# Schematic.net
KiCad netlist of a schematic drawn in Altium Designer
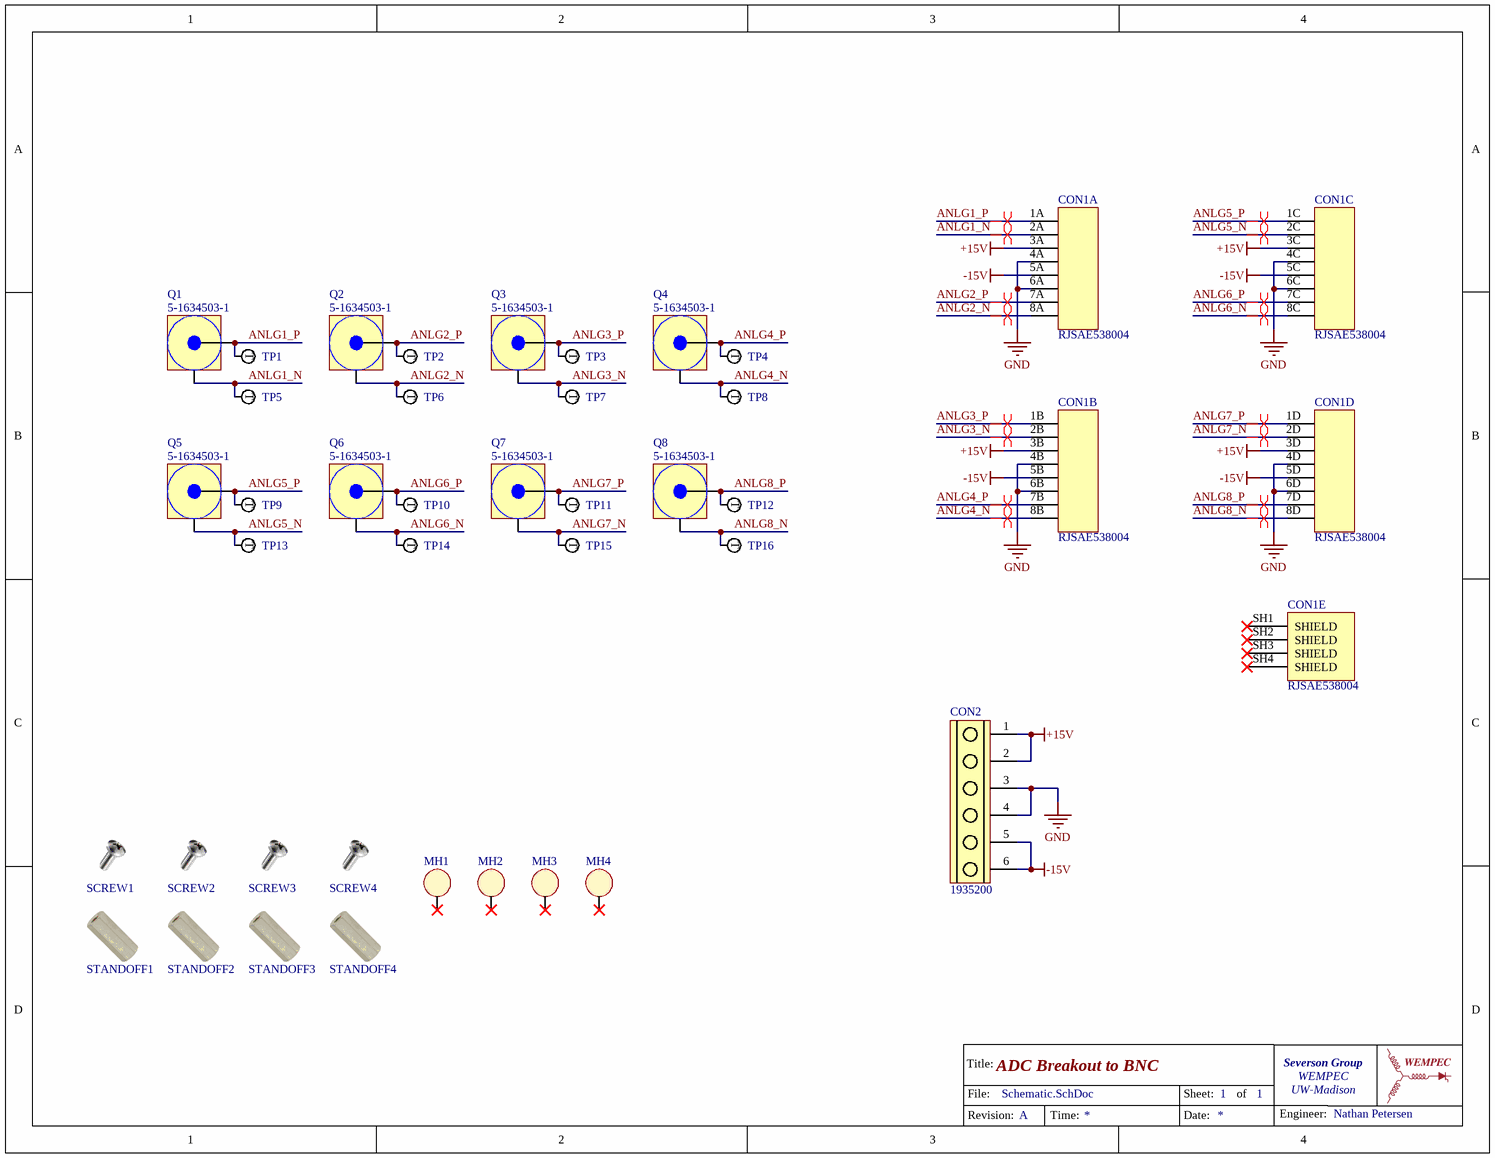
[diagram p0: Schematic.SchDoc]

(export (version "E")
  (design (tool "Eeschema 10.0.6"))
  (components
    (comp (ref "*1") (value "TitleBlockWEMPEC") (libsource (lib "AMDC") (part "TitleBlockWEMPEC")))
    (comp (ref "CON1")
      (value "RJSAE538004")
      (footprint "RJSAE538004")
      (description "CONN MOD JACK 8P8C R/A SHIELDED")
      (libsource (lib "AMDC") (part "RJSAE538004"))
    )
    (comp (ref "CON2")
      (value "1935200")
      (footprint "1935200")
      (description "TERM BLK 6POS SIDE ENTRY 5MM PCB")
      (libsource (lib "Schlib1") (part "1935200"))
    )
    (comp (ref "MH1")
      (value "MOUNT_HOLE")
      (footprint "AMDC:MOUNTING_HOLE")
      (description "MOUNTING HOLE")
      (libsource (lib "AMDC") (part "MOUNT_HOLE"))
    )
    (comp (ref "MH2")
      (value "MOUNT_HOLE")
      (footprint "AMDC:MOUNTING_HOLE")
      (description "MOUNTING HOLE")
      (libsource (lib "AMDC") (part "MOUNT_HOLE"))
    )
    (comp (ref "MH3")
      (value "MOUNT_HOLE")
      (footprint "AMDC:MOUNTING_HOLE")
      (description "MOUNTING HOLE")
      (libsource (lib "AMDC") (part "MOUNT_HOLE"))
    )
    (comp (ref "MH4")
      (value "MOUNT_HOLE")
      (footprint "AMDC:MOUNTING_HOLE")
      (description "MOUNTING HOLE")
      (libsource (lib "AMDC") (part "MOUNT_HOLE"))
    )
    (comp (ref "Q1")
      (value "5-1634503-1")
      (footprint "PcbLib:5-1634503-1")
      (description "BNC Connector Jack, Female Socket 50 Ohm Through Hole Solder")
      (libsource (lib "Schlib1") (part "5-1634503-1"))
    )
    (comp (ref "Q2")
      (value "5-1634503-1")
      (footprint "PcbLib:5-1634503-1")
      (description "BNC Connector Jack, Female Socket 50 Ohm Through Hole Solder")
      (libsource (lib "Schlib1") (part "5-1634503-1"))
    )
    (comp (ref "Q3")
      (value "5-1634503-1")
      (footprint "PcbLib:5-1634503-1")
      (description "BNC Connector Jack, Female Socket 50 Ohm Through Hole Solder")
      (libsource (lib "Schlib1") (part "5-1634503-1"))
    )
    (comp (ref "Q4")
      (value "5-1634503-1")
      (footprint "PcbLib:5-1634503-1")
      (description "BNC Connector Jack, Female Socket 50 Ohm Through Hole Solder")
      (libsource (lib "Schlib1") (part "5-1634503-1"))
    )
    (comp (ref "Q5")
      (value "5-1634503-1")
      (footprint "PcbLib:5-1634503-1")
      (description "BNC Connector Jack, Female Socket 50 Ohm Through Hole Solder")
      (libsource (lib "Schlib1") (part "5-1634503-1"))
    )
    (comp (ref "Q6")
      (value "5-1634503-1")
      (footprint "PcbLib:5-1634503-1")
      (description "BNC Connector Jack, Female Socket 50 Ohm Through Hole Solder")
      (libsource (lib "Schlib1") (part "5-1634503-1"))
    )
    (comp (ref "Q7")
      (value "5-1634503-1")
      (footprint "PcbLib:5-1634503-1")
      (description "BNC Connector Jack, Female Socket 50 Ohm Through Hole Solder")
      (libsource (lib "Schlib1") (part "5-1634503-1"))
    )
    (comp (ref "Q8")
      (value "5-1634503-1")
      (footprint "PcbLib:5-1634503-1")
      (description "BNC Connector Jack, Female Socket 50 Ohm Through Hole Solder")
      (libsource (lib "Schlib1") (part "5-1634503-1"))
    )
    (comp (ref "SCREW1") (value "Screw-4-40") (libsource (lib "AMDC") (part "Screw-4-40")))
    (comp (ref "SCREW2") (value "Screw-4-40") (libsource (lib "AMDC") (part "Screw-4-40")))
    (comp (ref "SCREW3") (value "Screw-4-40") (libsource (lib "AMDC") (part "Screw-4-40")))
    (comp (ref "SCREW4") (value "Screw-4-40") (libsource (lib "AMDC") (part "Screw-4-40")))
    (comp (ref "STANDOFF1") (value "Standoff-4-40") (libsource (lib "AMDC") (part "Standoff-4-40")))
    (comp (ref "STANDOFF2") (value "Standoff-4-40") (libsource (lib "AMDC") (part "Standoff-4-40")))
    (comp (ref "STANDOFF3") (value "Standoff-4-40") (libsource (lib "AMDC") (part "Standoff-4-40")))
    (comp (ref "STANDOFF4") (value "Standoff-4-40") (libsource (lib "AMDC") (part "Standoff-4-40")))
    (comp (ref "TP1")
      (value "Test Point")
      (footprint "TP_1.6MM")
      (libsource (lib "AMDC") (part "Test Point"))
    )
    (comp (ref "TP2")
      (value "Test Point")
      (footprint "TP_1.6MM")
      (libsource (lib "AMDC") (part "Test Point"))
    )
    (comp (ref "TP3")
      (value "Test Point")
      (footprint "TP_1.6MM")
      (libsource (lib "AMDC") (part "Test Point"))
    )
    (comp (ref "TP4")
      (value "Test Point")
      (footprint "TP_1.6MM")
      (libsource (lib "AMDC") (part "Test Point"))
    )
    (comp (ref "TP5")
      (value "Test Point")
      (footprint "TP_1.6MM")
      (libsource (lib "AMDC") (part "Test Point"))
    )
    (comp (ref "TP6")
      (value "Test Point")
      (footprint "TP_1.6MM")
      (libsource (lib "AMDC") (part "Test Point"))
    )
    (comp (ref "TP7")
      (value "Test Point")
      (footprint "TP_1.6MM")
      (libsource (lib "AMDC") (part "Test Point"))
    )
    (comp (ref "TP8")
      (value "Test Point")
      (footprint "TP_1.6MM")
      (libsource (lib "AMDC") (part "Test Point"))
    )
    (comp (ref "TP9")
      (value "Test Point")
      (footprint "TP_1.6MM")
      (libsource (lib "AMDC") (part "Test Point"))
    )
    (comp (ref "TP10")
      (value "Test Point")
      (footprint "TP_1.6MM")
      (libsource (lib "AMDC") (part "Test Point"))
    )
    (comp (ref "TP11")
      (value "Test Point")
      (footprint "TP_1.6MM")
      (libsource (lib "AMDC") (part "Test Point"))
    )
    (comp (ref "TP12")
      (value "Test Point")
      (footprint "TP_1.6MM")
      (libsource (lib "AMDC") (part "Test Point"))
    )
    (comp (ref "TP13")
      (value "Test Point")
      (footprint "TP_1.6MM")
      (libsource (lib "AMDC") (part "Test Point"))
    )
    (comp (ref "TP14")
      (value "Test Point")
      (footprint "TP_1.6MM")
      (libsource (lib "AMDC") (part "Test Point"))
    )
    (comp (ref "TP15")
      (value "Test Point")
      (footprint "TP_1.6MM")
      (libsource (lib "AMDC") (part "Test Point"))
    )
    (comp (ref "TP16")
      (value "Test Point")
      (footprint "TP_1.6MM")
      (libsource (lib "AMDC") (part "Test Point"))
    )
  )
  (nets
    (net (code "1") (name "+15V") (class "Default")
      (node (ref "CON1") (pin "3A") (pinfunction "79_3A") (pintype "passive"))
      (node (ref "CON1") (pin "3B") (pinfunction "79_3B") (pintype "passive"))
      (node (ref "CON1") (pin "3C") (pinfunction "79_3C") (pintype "passive"))
      (node (ref "CON1") (pin "3D") (pinfunction "79_3D") (pintype "passive"))
      (node (ref "CON2") (pin "1") (pinfunction "1_1") (pintype "passive"))
      (node (ref "CON2") (pin "2") (pinfunction "2_2") (pintype "passive"))
    )
    (net (code "2") (name "-15V") (class "Default")
      (node (ref "CON1") (pin "5A") (pinfunction "79_5A") (pintype "passive"))
      (node (ref "CON1") (pin "5B") (pinfunction "79_5B") (pintype "passive"))
      (node (ref "CON1") (pin "5C") (pinfunction "79_5C") (pintype "passive"))
      (node (ref "CON1") (pin "5D") (pinfunction "79_5D") (pintype "passive"))
      (node (ref "CON2") (pin "5") (pinfunction "5_5") (pintype "passive"))
      (node (ref "CON2") (pin "6") (pinfunction "6_6") (pintype "passive"))
    )
    (net (code "3") (name "/ANLG1_N") (class "Default")
      (node (ref "CON1") (pin "2A") (pinfunction "79_2A") (pintype "passive"))
      (node (ref "Q1") (pin "2") (pinfunction "2_2") (pintype "passive"))
      (node (ref "TP5") (pin "1") (pinfunction "1_1") (pintype "passive"))
    )
    (net (code "4") (name "/ANLG1_P") (class "Default")
      (node (ref "CON1") (pin "1A") (pinfunction "79_1A") (pintype "passive"))
      (node (ref "Q1") (pin "1") (pinfunction "1_1") (pintype "passive"))
      (node (ref "TP1") (pin "1") (pinfunction "1_1") (pintype "passive"))
    )
    (net (code "5") (name "/ANLG2_N") (class "Default")
      (node (ref "CON1") (pin "8A") (pinfunction "79_8A") (pintype "passive"))
      (node (ref "Q2") (pin "2") (pinfunction "2_2") (pintype "passive"))
      (node (ref "TP6") (pin "1") (pinfunction "1_1") (pintype "passive"))
    )
    (net (code "6") (name "/ANLG2_P") (class "Default")
      (node (ref "CON1") (pin "7A") (pinfunction "79_7A") (pintype "passive"))
      (node (ref "Q2") (pin "1") (pinfunction "1_1") (pintype "passive"))
      (node (ref "TP2") (pin "1") (pinfunction "1_1") (pintype "passive"))
    )
    (net (code "7") (name "/ANLG3_N") (class "Default")
      (node (ref "CON1") (pin "2B") (pinfunction "79_2B") (pintype "passive"))
      (node (ref "Q3") (pin "2") (pinfunction "2_2") (pintype "passive"))
      (node (ref "TP7") (pin "1") (pinfunction "1_1") (pintype "passive"))
    )
    (net (code "8") (name "/ANLG3_P") (class "Default")
      (node (ref "CON1") (pin "1B") (pinfunction "79_1B") (pintype "passive"))
      (node (ref "Q3") (pin "1") (pinfunction "1_1") (pintype "passive"))
      (node (ref "TP3") (pin "1") (pinfunction "1_1") (pintype "passive"))
    )
    (net (code "9") (name "/ANLG4_N") (class "Default")
      (node (ref "CON1") (pin "8B") (pinfunction "79_8B") (pintype "passive"))
      (node (ref "Q4") (pin "2") (pinfunction "2_2") (pintype "passive"))
      (node (ref "TP8") (pin "1") (pinfunction "1_1") (pintype "passive"))
    )
    (net (code "10") (name "/ANLG4_P") (class "Default")
      (node (ref "CON1") (pin "7B") (pinfunction "79_7B") (pintype "passive"))
      (node (ref "Q4") (pin "1") (pinfunction "1_1") (pintype "passive"))
      (node (ref "TP4") (pin "1") (pinfunction "1_1") (pintype "passive"))
    )
    (net (code "11") (name "/ANLG5_N") (class "Default")
      (node (ref "CON1") (pin "2C") (pinfunction "79_2C") (pintype "passive"))
      (node (ref "Q5") (pin "2") (pinfunction "2_2") (pintype "passive"))
      (node (ref "TP13") (pin "1") (pinfunction "1_1") (pintype "passive"))
    )
    (net (code "12") (name "/ANLG5_P") (class "Default")
      (node (ref "CON1") (pin "1C") (pinfunction "79_1C") (pintype "passive"))
      (node (ref "Q5") (pin "1") (pinfunction "1_1") (pintype "passive"))
      (node (ref "TP9") (pin "1") (pinfunction "1_1") (pintype "passive"))
    )
    (net (code "13") (name "/ANLG6_N") (class "Default")
      (node (ref "CON1") (pin "8C") (pinfunction "79_8C") (pintype "passive"))
      (node (ref "Q6") (pin "2") (pinfunction "2_2") (pintype "passive"))
      (node (ref "TP14") (pin "1") (pinfunction "1_1") (pintype "passive"))
    )
    (net (code "14") (name "/ANLG6_P") (class "Default")
      (node (ref "CON1") (pin "7C") (pinfunction "79_7C") (pintype "passive"))
      (node (ref "Q6") (pin "1") (pinfunction "1_1") (pintype "passive"))
      (node (ref "TP10") (pin "1") (pinfunction "1_1") (pintype "passive"))
    )
    (net (code "15") (name "/ANLG7_N") (class "Default")
      (node (ref "CON1") (pin "2D") (pinfunction "79_2D") (pintype "passive"))
      (node (ref "Q7") (pin "2") (pinfunction "2_2") (pintype "passive"))
      (node (ref "TP15") (pin "1") (pinfunction "1_1") (pintype "passive"))
    )
    (net (code "16") (name "/ANLG7_P") (class "Default")
      (node (ref "CON1") (pin "1D") (pinfunction "79_1D") (pintype "passive"))
      (node (ref "Q7") (pin "1") (pinfunction "1_1") (pintype "passive"))
      (node (ref "TP11") (pin "1") (pinfunction "1_1") (pintype "passive"))
    )
    (net (code "17") (name "/ANLG8_N") (class "Default")
      (node (ref "CON1") (pin "8D") (pinfunction "79_8D") (pintype "passive"))
      (node (ref "Q8") (pin "2") (pinfunction "2_2") (pintype "passive"))
      (node (ref "TP16") (pin "1") (pinfunction "1_1") (pintype "passive"))
    )
    (net (code "18") (name "/ANLG8_P") (class "Default")
      (node (ref "CON1") (pin "7D") (pinfunction "79_7D") (pintype "passive"))
      (node (ref "Q8") (pin "1") (pinfunction "1_1") (pintype "passive"))
      (node (ref "TP12") (pin "1") (pinfunction "1_1") (pintype "passive"))
    )
    (net (code "19") (name "GND") (class "Default")
      (node (ref "CON1") (pin "4A") (pinfunction "79_4A") (pintype "passive"))
      (node (ref "CON1") (pin "4B") (pinfunction "79_4B") (pintype "passive"))
      (node (ref "CON1") (pin "4C") (pinfunction "79_4C") (pintype "passive"))
      (node (ref "CON1") (pin "4D") (pinfunction "79_4D") (pintype "passive"))
      (node (ref "CON1") (pin "6A") (pinfunction "79_6A") (pintype "passive"))
      (node (ref "CON1") (pin "6B") (pinfunction "79_6B") (pintype "passive"))
      (node (ref "CON1") (pin "6C") (pinfunction "79_6C") (pintype "passive"))
      (node (ref "CON1") (pin "6D") (pinfunction "79_6D") (pintype "passive"))
      (node (ref "CON2") (pin "3") (pinfunction "3_3") (pintype "passive"))
      (node (ref "CON2") (pin "4") (pinfunction "4_4") (pintype "passive"))
    )
    (net (code "20") (name "unconnected-(CON1E-SHIELD-PadSH1)") (class "Default")
      (node (ref "CON1") (pin "SH1") (pinfunction "SHIELD_SH1") (pintype "passive+no_connect"))
    )
    (net (code "21") (name "unconnected-(CON1E-SHIELD-PadSH2)") (class "Default")
      (node (ref "CON1") (pin "SH2") (pinfunction "SHIELD_SH2") (pintype "passive+no_connect"))
    )
    (net (code "22") (name "unconnected-(CON1E-SHIELD-PadSH3)") (class "Default")
      (node (ref "CON1") (pin "SH3") (pinfunction "SHIELD_SH3") (pintype "passive+no_connect"))
    )
    (net (code "23") (name "unconnected-(CON1E-SHIELD-PadSH4)") (class "Default")
      (node (ref "CON1") (pin "SH4") (pinfunction "SHIELD_SH4") (pintype "passive+no_connect"))
    )
    (net (code "24") (name "unconnected-(MH1-Pad1)") (class "Default")
      (node (ref "MH1") (pin "1") (pinfunction "1_1") (pintype "passive+no_connect"))
    )
    (net (code "25") (name "unconnected-(MH2-Pad1)") (class "Default")
      (node (ref "MH2") (pin "1") (pinfunction "1_1") (pintype "passive+no_connect"))
    )
    (net (code "26") (name "unconnected-(MH3-Pad1)") (class "Default")
      (node (ref "MH3") (pin "1") (pinfunction "1_1") (pintype "passive+no_connect"))
    )
    (net (code "27") (name "unconnected-(MH4-Pad1)") (class "Default")
      (node (ref "MH4") (pin "1") (pinfunction "1_1") (pintype "passive+no_connect"))
    )
  )
)
